# Flow_sensor.net
KiCad netlist of a schematic drawn in Altium Designer
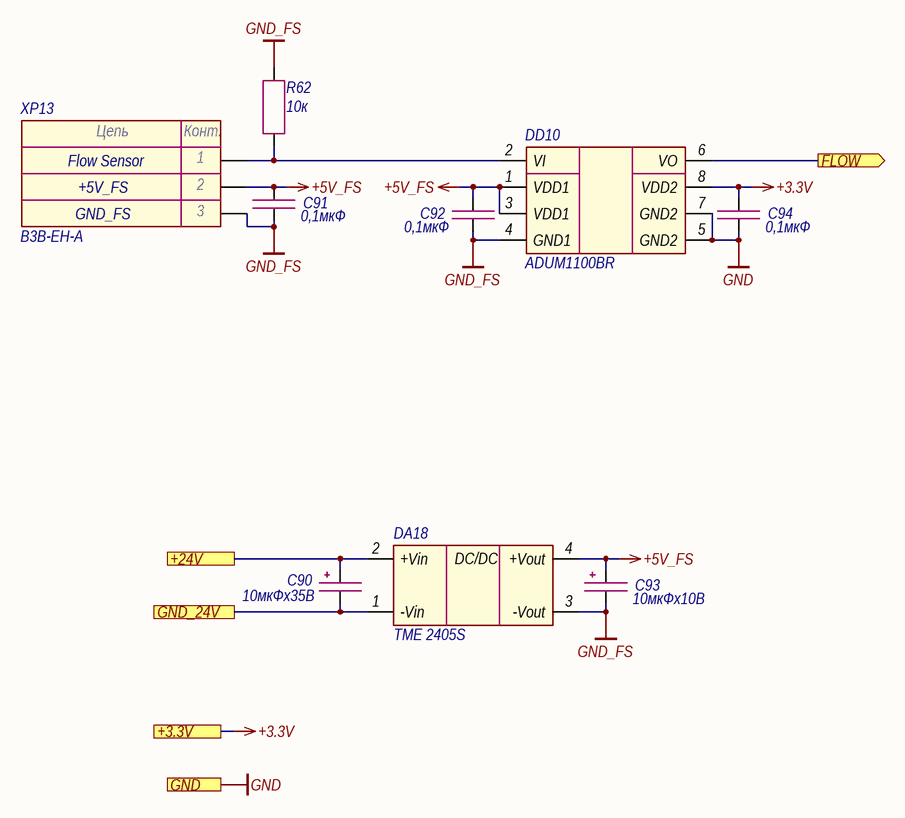
[diagram p0: Flow_sensor.SchDoc]

(export (version "E")
  (design (tool "Eeschema 10.0.6"))
  (components
    (comp (ref "C90")
      (value "10мкФх35B")
      (footprint "Pcb_library:CAP_C")
      (libsource (lib "Schem_library") (part "Capacitor_Polar"))
    )
    (comp (ref "C91")
      (value "0,1мкФ")
      (footprint "Pcb_library:CAP_0603")
      (fields (field (name "MANUFACTURER") "Murata"))
      (libsource (lib "Schem_library") (part "Capacitor"))
    )
    (comp (ref "C92")
      (value "0,1мкФ")
      (footprint "Pcb_library:CAP_0603")
      (fields (field (name "MANUFACTURER") "Murata"))
      (libsource (lib "Schem_library") (part "Capacitor"))
    )
    (comp (ref "C93")
      (value "10мкФх10B")
      (footprint "Pcb_library:CAP_A")
      (libsource (lib "Schem_library") (part "Capacitor_Polar"))
    )
    (comp (ref "C94")
      (value "0,1мкФ")
      (footprint "Pcb_library:CAP_0603")
      (fields (field (name "MANUFACTURER") "Murata"))
      (libsource (lib "Schem_library") (part "Capacitor"))
    )
    (comp (ref "DA18")
      (value "TME 2405S")
      (footprint "Pcb_library:TME (SIP-4)")
      (fields (field (name "MANUFACTURER") "Traco Power"))
      (libsource (lib "Schem_library") (part "TME"))
    )
    (comp (ref "DD10")
      (value "ADUM1100BR")
      (footprint "Pcb_library:SOIC-8")
      (fields (field (name "MANUFACTURER") "Analog Devices"))
      (libsource (lib "Schem_library") (part "ADUM1100"))
    )
    (comp (ref "R62")
      (value "10к")
      (footprint "Pcb_library:RES_0603")
      (fields (field (name "MANUFACTURER") "Yageo"))
      (libsource (lib "Schem_library") (part "Resistor"))
    )
    (comp (ref "XP13")
      (value "B3B-EH-A")
      (footprint "B3B-EH-A")
      (fields (field (name "MANUFACTURER") "JST"))
      (libsource (lib "Schem_library") (part "Connector-3"))
    )
  )
  (nets
    (net (code "1") (name "+3.3V") (class "Default")
      (node (ref "C94") (pin "1") (pinfunction "1_1") (pintype "passive"))
      (node (ref "DD10") (pin "8") (pinfunction "VDD2_8") (pintype "passive"))
    )
    (net (code "2") (name "+5V_FS") (class "Default")
      (node (ref "C91") (pin "1") (pinfunction "1_1") (pintype "passive"))
      (node (ref "C92") (pin "1") (pinfunction "1_1") (pintype "passive"))
      (node (ref "C93") (pin "1") (pinfunction "1_1") (pintype "passive"))
      (node (ref "DA18") (pin "4") (pinfunction "+Vout_4") (pintype "passive"))
      (node (ref "DD10") (pin "1") (pinfunction "VDD1_1") (pintype "passive"))
      (node (ref "DD10") (pin "3") (pinfunction "VDD1_3") (pintype "passive"))
      (node (ref "XP13") (pin "2") (pintype "passive"))
    )
    (net (code "3") (name "/+24V") (class "Default")
      (node (ref "C90") (pin "1") (pinfunction "1_1") (pintype "passive"))
      (node (ref "DA18") (pin "2") (pinfunction "+Vin_2") (pintype "passive"))
    )
    (net (code "4") (name "/FLOW") (class "Default")
      (node (ref "DD10") (pin "6") (pinfunction "VO_6") (pintype "passive"))
    )
    (net (code "5") (name "/GND_24V") (class "Default")
      (node (ref "C90") (pin "2") (pinfunction "2_2") (pintype "passive"))
      (node (ref "DA18") (pin "1") (pinfunction "-Vin_1") (pintype "passive"))
    )
    (net (code "6") (name "GND") (class "Default")
      (node (ref "C94") (pin "2") (pinfunction "2_2") (pintype "passive"))
      (node (ref "DD10") (pin "5") (pinfunction "GND2_5") (pintype "passive"))
      (node (ref "DD10") (pin "7") (pinfunction "GND2_7") (pintype "passive"))
    )
    (net (code "7") (name "GND_FS") (class "Default")
      (node (ref "C91") (pin "2") (pinfunction "2_2") (pintype "passive"))
      (node (ref "C92") (pin "2") (pinfunction "2_2") (pintype "passive"))
      (node (ref "C93") (pin "2") (pinfunction "2_2") (pintype "passive"))
      (node (ref "DA18") (pin "3") (pinfunction "-Vout_3") (pintype "passive"))
      (node (ref "DD10") (pin "4") (pinfunction "GND1_4") (pintype "passive"))
      (node (ref "R62") (pin "2") (pinfunction "2_2") (pintype "passive"))
      (node (ref "XP13") (pin "3") (pintype "passive"))
    )
    (net (code "8") (name "Net-(DD10-VI)") (class "Default")
      (node (ref "DD10") (pin "2") (pinfunction "VI_2") (pintype "passive"))
      (node (ref "R62") (pin "1") (pinfunction "1_1") (pintype "passive"))
      (node (ref "XP13") (pin "1") (pintype "passive"))
    )
  )
)
